# DC-DC_v3.net
KiCad netlist of a schematic drawn in EAGLE
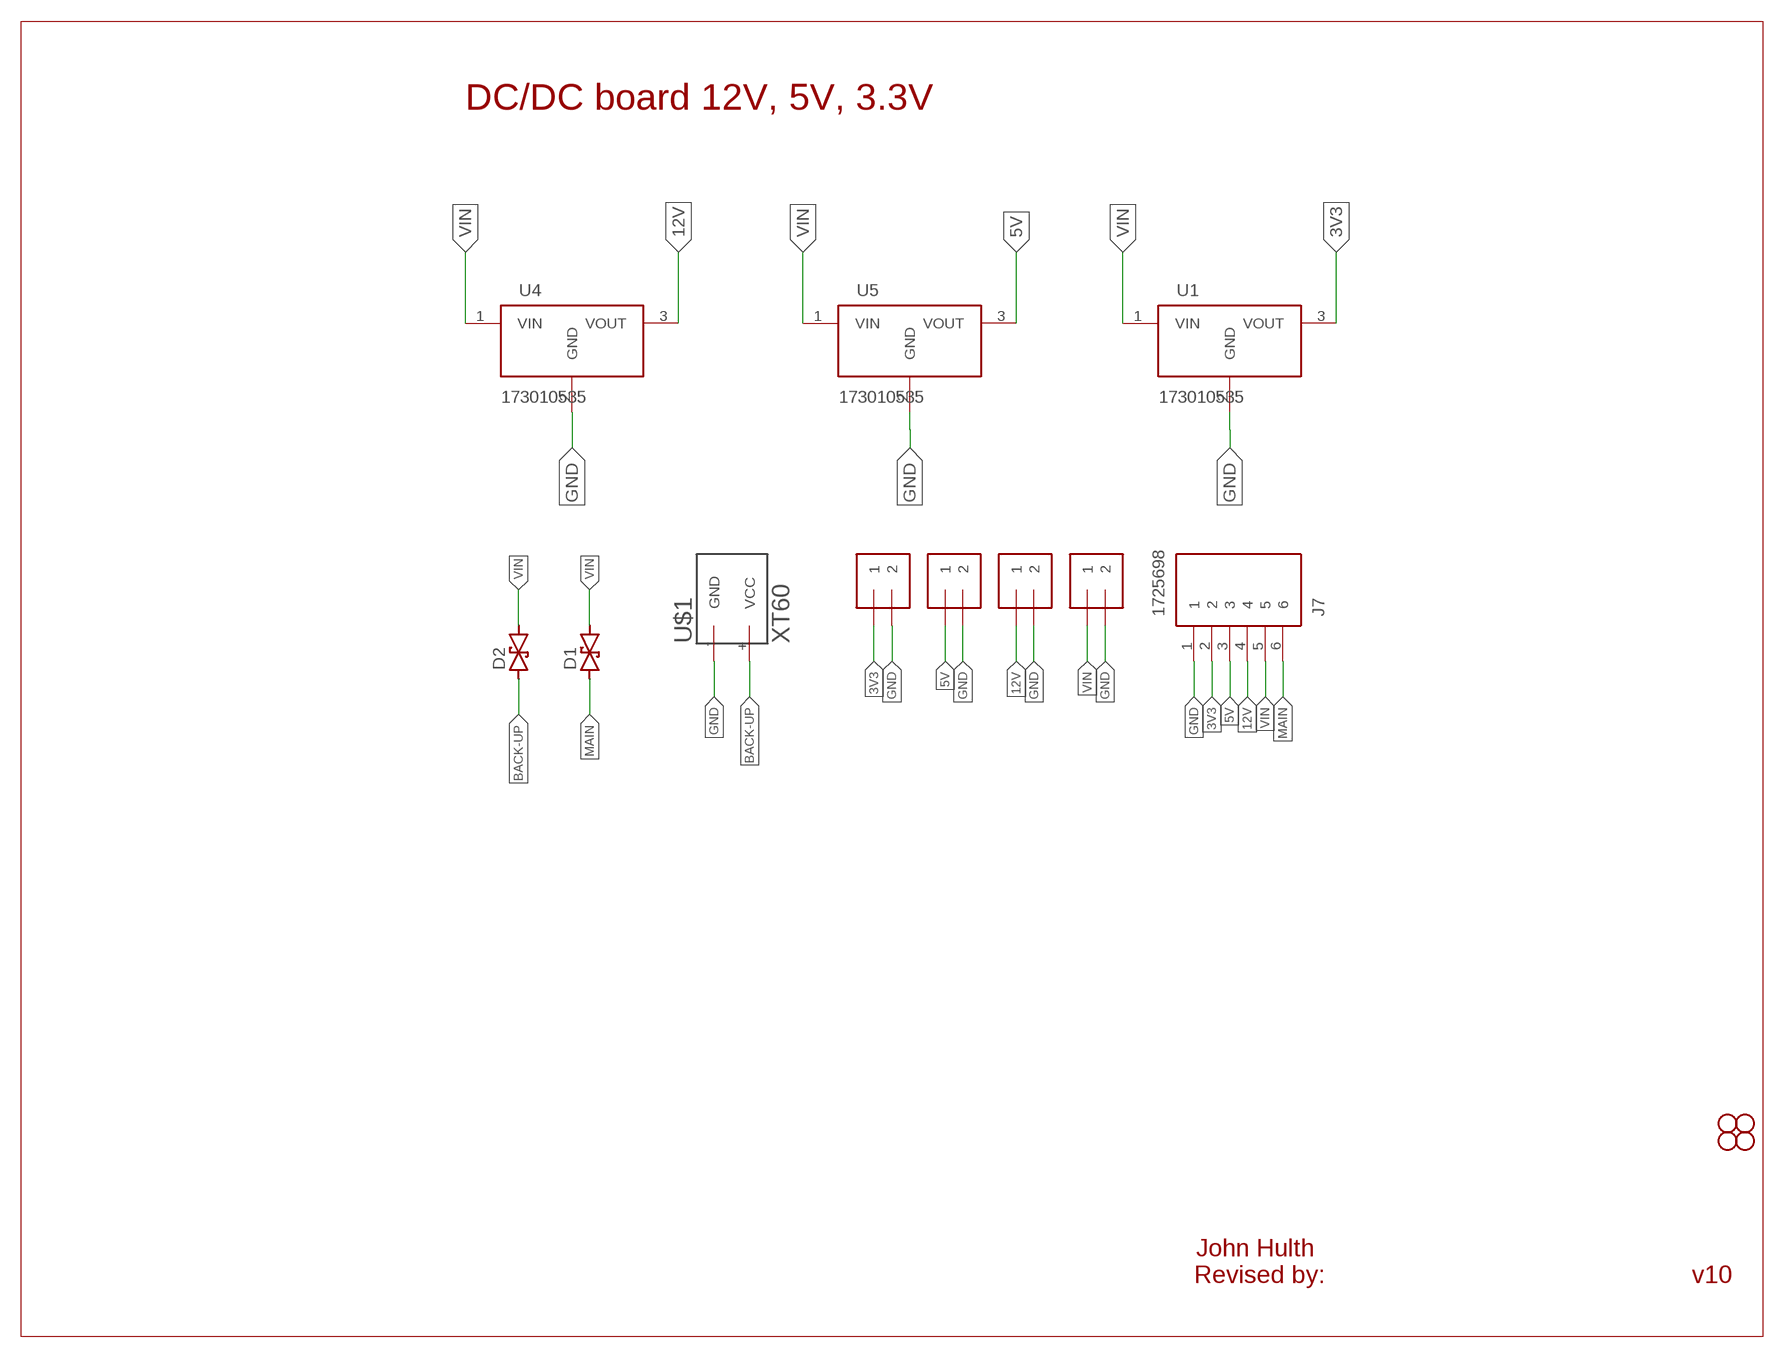
[diagram p0: schematic, sheet 1]

(export (version "E")
  (design (tool "Eeschema 10.0.6"))
  (components
    (comp (ref "D1")
      (value "DIODE_SCHOTTKY2-P2-15")
      (footprint "eagle-import:P2-15")
      (libsource (lib "eagle-import") (part "DIODE_SCHOTTKY2-P2-15"))
    )
    (comp (ref "D2")
      (value "DIODE_SCHOTTKY2-P2-15")
      (footprint "eagle-import:P2-15")
      (libsource (lib "eagle-import") (part "DIODE_SCHOTTKY2-P2-15"))
    )
    (comp (ref "J2")
      (value "1X2-3.5MM")
      (footprint "eagle-import:1X2-3.5MM")
      (libsource (lib "eagle-import") (part "1X2-3.5MM"))
    )
    (comp (ref "J3")
      (value "1X2-3.5MM")
      (footprint "eagle-import:1X2-3.5MM")
      (libsource (lib "eagle-import") (part "1X2-3.5MM"))
    )
    (comp (ref "J4")
      (value "1X2-3.5MM")
      (footprint "eagle-import:1X2-3.5MM")
      (libsource (lib "eagle-import") (part "1X2-3.5MM"))
    )
    (comp (ref "J5")
      (value "1X2-3.5MM")
      (footprint "eagle-import:1X2-3.5MM")
      (libsource (lib "eagle-import") (part "1X2-3.5MM"))
    )
    (comp (ref "J7")
      (value "1725698")
      (footprint "eagle-import:SHDR6W90P0X254_1X6_1570X620X85")
      (fields (field (name "RS_PART_NUMBER") "3909045"))
      (libsource (lib "eagle-import") (part "1725698"))
    )
    (comp (ref "JP2")
      (value "STAND-OFF")
      (footprint "eagle-import:STAND-OFF")
      (libsource (lib "eagle-import") (part "STAND-OFF"))
    )
    (comp (ref "JP3")
      (value "STAND-OFF")
      (footprint "eagle-import:STAND-OFF")
      (libsource (lib "eagle-import") (part "STAND-OFF"))
    )
    (comp (ref "JP8")
      (value "STAND-OFF")
      (footprint "eagle-import:STAND-OFF")
      (libsource (lib "eagle-import") (part "STAND-OFF"))
    )
    (comp (ref "JP9")
      (value "STAND-OFF")
      (footprint "eagle-import:STAND-OFF")
      (libsource (lib "eagle-import") (part "STAND-OFF"))
    )
    (comp (ref "U$1")
      (value "XT60")
      (footprint "eagle-import:XT60")
      (libsource (lib "eagle-import") (part "XT60"))
    )
    (comp (ref "U1")
      (value "173010535")
      (footprint "eagle-import:173010535")
      (fields
        (field (name "DIGIKEY_PARTNO") "732-173010535-ND")
        (field (name "MANUFACTURER") "Würth Elektronik")
        (field (name "CREATED_BY") "PCBLayout.com")
      )
      (libsource (lib "eagle-import") (part "173010535"))
    )
    (comp (ref "U4")
      (value "173010535")
      (footprint "eagle-import:173010535")
      (fields
        (field (name "DIGIKEY_PARTNO") "732-173010535-ND")
        (field (name "MANUFACTURER") "Würth Elektronik")
        (field (name "CREATED_BY") "PCBLayout.com")
      )
      (libsource (lib "eagle-import") (part "173010535"))
    )
    (comp (ref "U5")
      (value "173010535")
      (footprint "eagle-import:173010535")
      (fields
        (field (name "DIGIKEY_PARTNO") "732-173010535-ND")
        (field (name "MANUFACTURER") "Würth Elektronik")
        (field (name "CREATED_BY") "PCBLayout.com")
      )
      (libsource (lib "eagle-import") (part "173010535"))
    )
  )
  (nets
    (net (code "1") (name "3V3") (class "Default")
      (node (ref "J2") (pin "1") (pinfunction "1_1") (pintype "passive"))
      (node (ref "J7") (pin "2") (pinfunction "2_2") (pintype "bidirectional"))
      (node (ref "U1") (pin "3") (pinfunction "VOUT_3") (pintype "power_in"))
    )
    (net (code "2") (name "5V") (class "Default")
      (node (ref "J3") (pin "1") (pinfunction "1_1") (pintype "passive"))
      (node (ref "J7") (pin "3") (pinfunction "3_3") (pintype "bidirectional"))
      (node (ref "U5") (pin "3") (pinfunction "VOUT_3") (pintype "power_in"))
    )
    (net (code "3") (name "12V") (class "Default")
      (node (ref "J4") (pin "1") (pinfunction "1_1") (pintype "passive"))
      (node (ref "J7") (pin "4") (pinfunction "4_4") (pintype "bidirectional"))
      (node (ref "U4") (pin "3") (pinfunction "VOUT_3") (pintype "power_in"))
    )
    (net (code "4") (name "BACK-UP") (class "Default")
      (node (ref "D2") (pin "A") (pinfunction "1_A") (pintype "passive"))
      (node (ref "U$1") (pin "+") (pinfunction "VCC_+") (pintype "bidirectional"))
    )
    (net (code "5") (name "GND") (class "Default")
      (node (ref "J2") (pin "2") (pinfunction "2_2") (pintype "passive"))
      (node (ref "J3") (pin "2") (pinfunction "2_2") (pintype "passive"))
      (node (ref "J4") (pin "2") (pinfunction "2_2") (pintype "passive"))
      (node (ref "J5") (pin "2") (pinfunction "2_2") (pintype "passive"))
      (node (ref "J7") (pin "1") (pinfunction "1_1") (pintype "bidirectional"))
      (node (ref "U$1") (pin "-") (pinfunction "GND_-") (pintype "bidirectional"))
      (node (ref "U1") (pin "2") (pinfunction "GND_2") (pintype "power_in"))
      (node (ref "U4") (pin "2") (pinfunction "GND_2") (pintype "power_in"))
      (node (ref "U5") (pin "2") (pinfunction "GND_2") (pintype "power_in"))
    )
    (net (code "6") (name "MAIN") (class "Default")
      (node (ref "D1") (pin "A") (pinfunction "1_A") (pintype "passive"))
      (node (ref "J7") (pin "6") (pinfunction "6_6") (pintype "bidirectional"))
    )
    (net (code "7") (name "VIN") (class "Default")
      (node (ref "D1") (pin "C") (pinfunction "2_C") (pintype "passive"))
      (node (ref "D2") (pin "C") (pinfunction "2_C") (pintype "passive"))
      (node (ref "J5") (pin "1") (pinfunction "1_1") (pintype "passive"))
      (node (ref "J7") (pin "5") (pinfunction "5_5") (pintype "bidirectional"))
      (node (ref "U1") (pin "1") (pinfunction "VIN_1") (pintype "power_in"))
      (node (ref "U4") (pin "1") (pinfunction "VIN_1") (pintype "power_in"))
      (node (ref "U5") (pin "1") (pinfunction "VIN_1") (pintype "power_in"))
    )
  )
)
